# CubeSat_Backplane.net
KiCad netlist of a schematic drawn in Altium Designer
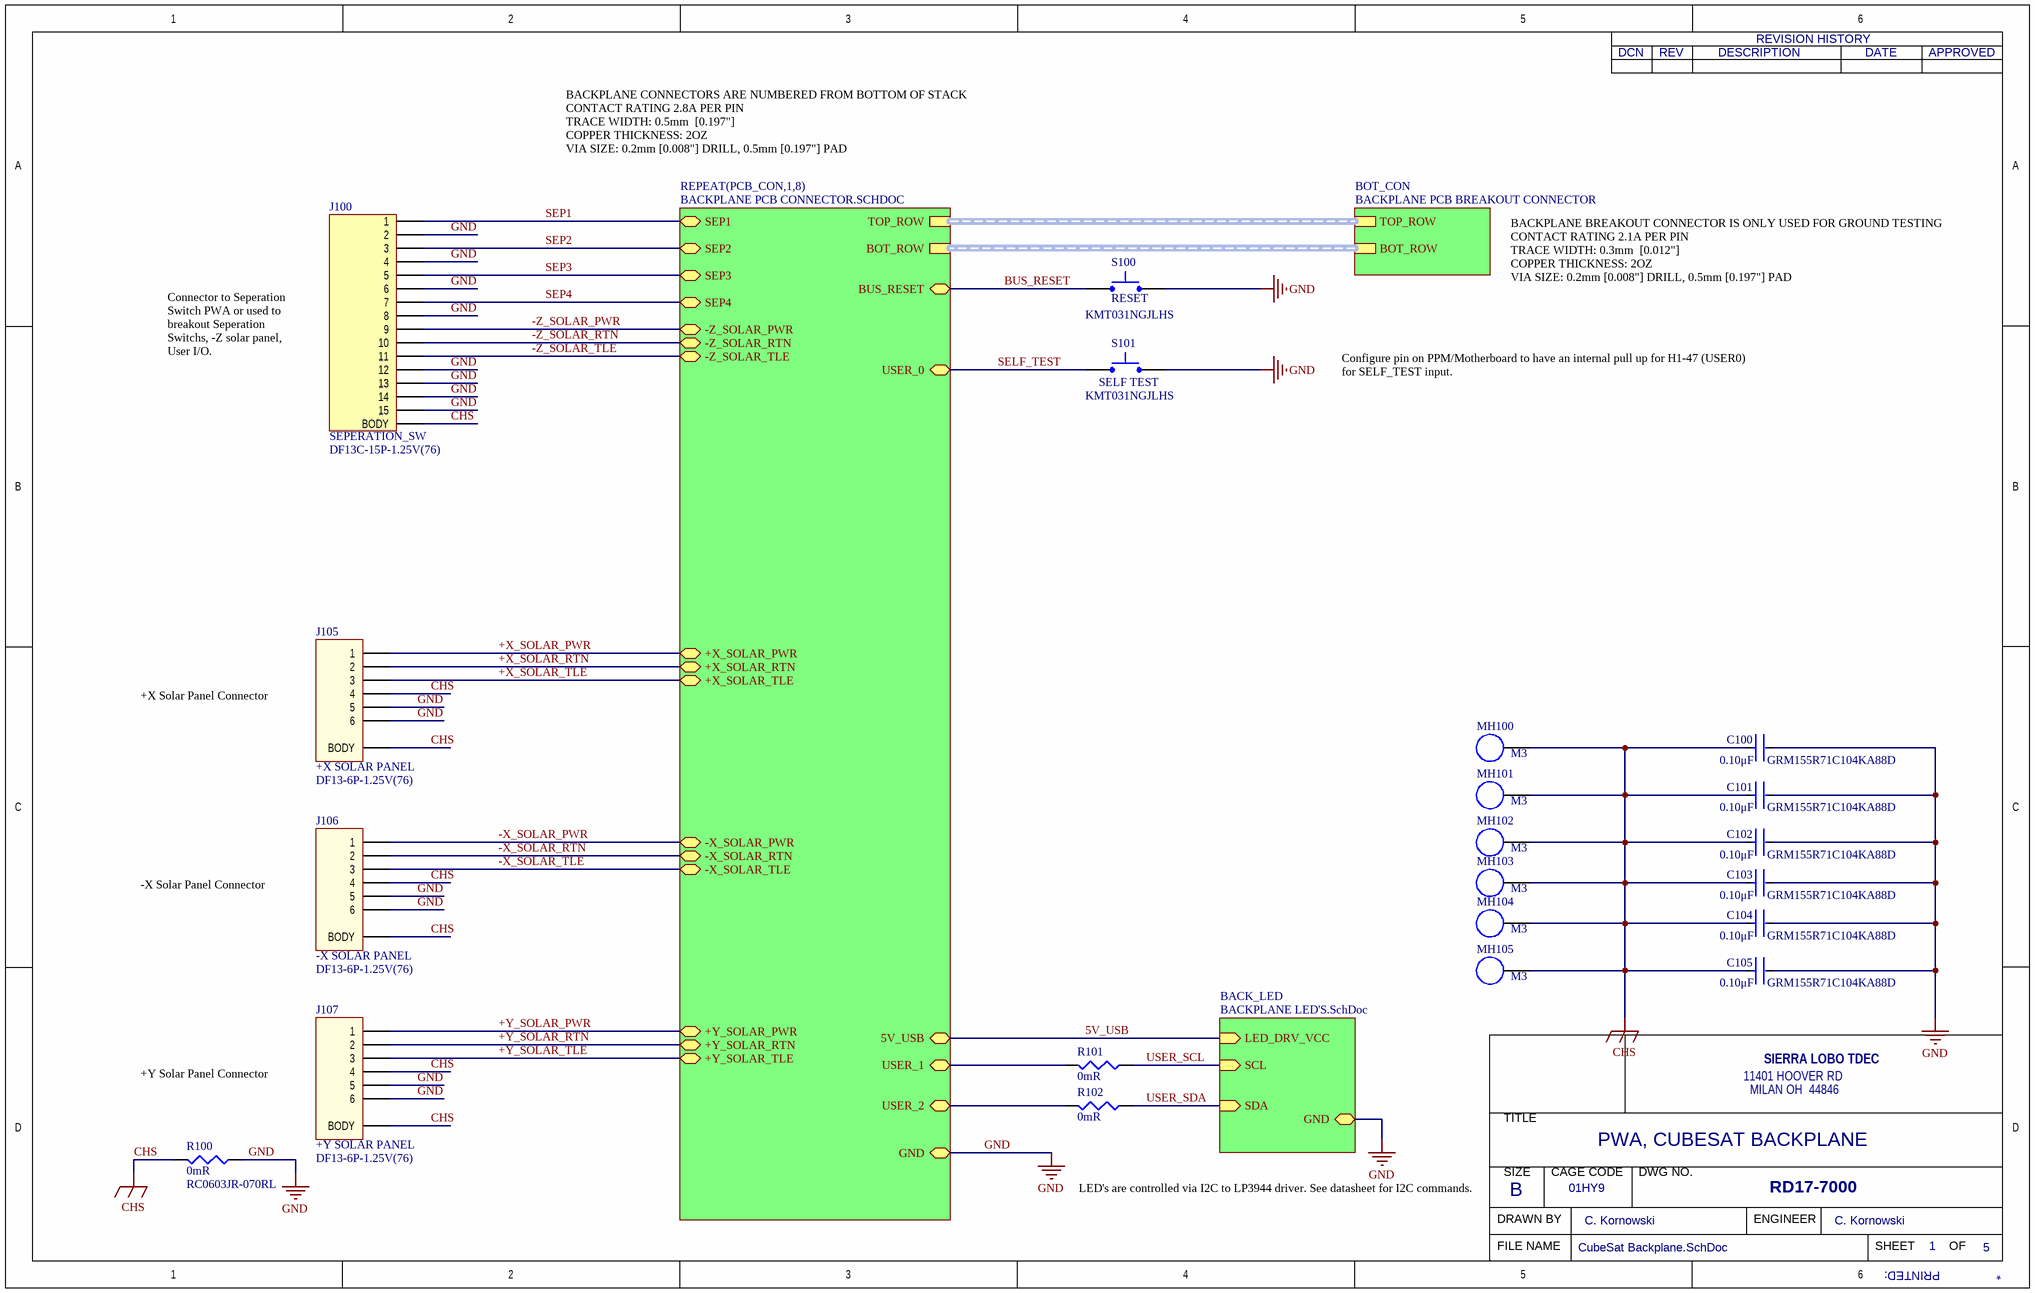
[diagram p0: CubeSat Backplane.SchDoc]

(export (version "E")
  (design (tool "Eeschema 10.0.6"))
  (components
    (comp (ref "C100")
      (value "GRM155R71C104KA88D")
      (footprint "FP-GRM15-MFG")
      (description "CAP CER 0.1UF 16V X7R 0402")
      (fields
        (field (name "TOLERANCE") "10%")
        (field (name "OCTOPART") "https://octopart.com/grm155r71c104ka88d-murata-196880")
        (field (name "CAPACITANCE") "0.10μF")
      )
      (libsource (lib "Altium Content Vault") (part "236180d848d6139a670b325ea6854c9"))
    )
    (comp (ref "C101")
      (value "GRM155R71C104KA88D")
      (footprint "FP-GRM15-MFG")
      (description "CAP CER 0.1UF 16V X7R 0402")
      (fields
        (field (name "TOLERANCE") "10%")
        (field (name "OCTOPART") "https://octopart.com/grm155r71c104ka88d-murata-196880")
        (field (name "CAPACITANCE") "0.10μF")
      )
      (libsource (lib "Altium Content Vault") (part "236180d848d6139a670b325ea6854c9"))
    )
    (comp (ref "C102")
      (value "GRM155R71C104KA88D")
      (footprint "FP-GRM15-MFG")
      (description "CAP CER 0.1UF 16V X7R 0402")
      (fields
        (field (name "TOLERANCE") "10%")
        (field (name "OCTOPART") "https://octopart.com/grm155r71c104ka88d-murata-196880")
        (field (name "CAPACITANCE") "0.10μF")
      )
      (libsource (lib "Altium Content Vault") (part "236180d848d6139a670b325ea6854c9"))
    )
    (comp (ref "C103")
      (value "GRM155R71C104KA88D")
      (footprint "FP-GRM15-MFG")
      (description "CAP CER 0.1UF 16V X7R 0402")
      (fields
        (field (name "TOLERANCE") "10%")
        (field (name "OCTOPART") "https://octopart.com/grm155r71c104ka88d-murata-196880")
        (field (name "CAPACITANCE") "0.10μF")
      )
      (libsource (lib "Altium Content Vault") (part "236180d848d6139a670b325ea6854c9"))
    )
    (comp (ref "C104")
      (value "GRM155R71C104KA88D")
      (footprint "FP-GRM15-MFG")
      (description "CAP CER 0.1UF 16V X7R 0402")
      (fields
        (field (name "TOLERANCE") "10%")
        (field (name "OCTOPART") "https://octopart.com/grm155r71c104ka88d-murata-196880")
        (field (name "CAPACITANCE") "0.10μF")
      )
      (libsource (lib "Altium Content Vault") (part "236180d848d6139a670b325ea6854c9"))
    )
    (comp (ref "C105")
      (value "GRM155R71C104KA88D")
      (footprint "FP-GRM15-MFG")
      (description "CAP CER 0.1UF 16V X7R 0402")
      (fields
        (field (name "TOLERANCE") "10%")
        (field (name "OCTOPART") "https://octopart.com/grm155r71c104ka88d-murata-196880")
        (field (name "CAPACITANCE") "0.10μF")
      )
      (libsource (lib "Altium Content Vault") (part "236180d848d6139a670b325ea6854c9"))
    )
    (comp (ref "J100")
      (value "SEPERATION_SW")
      (footprint "DF13-15P-1.25H(75)")
      (description "CONN HEADER SMD R/A 15POS 1.25MM")
      (fields
        (field (name "MANUFACTURER") "Hirose")
        (field (name "MANUFACTURER PART NUMBER") "DF13C-15P-1.25V(76)")
      )
      (libsource (lib "CubeSat-Backplane") (part "DF13C-15P-1.25x"))
    )
    (comp (ref "J105")
      (value "+X SOLAR PANEL")
      (footprint "DF13-6P-1.25V(75)")
      (description "CONN HEADER SMD 6POS 1.25MM")
      (fields (field (name "MANUFACTURER PART NUMBER 1") "DF13-6P-1.25V(76)"))
      (libsource (lib "CubeSat-Backplane") (part "DF13-6P-1.25V(76)"))
    )
    (comp (ref "J106")
      (value "-X SOLAR PANEL")
      (footprint "DF13-6P-1.25V(75)")
      (description "CONN HEADER SMD 6POS 1.25MM")
      (fields (field (name "MANUFACTURER PART NUMBER 1") "DF13-6P-1.25V(76)"))
      (libsource (lib "CubeSat-Backplane") (part "DF13-6P-1.25V(76)"))
    )
    (comp (ref "J107")
      (value "+Y SOLAR PANEL")
      (footprint "DF13-6P-1.25V(75)")
      (description "CONN HEADER SMD 6POS 1.25MM")
      (fields (field (name "MANUFACTURER PART NUMBER 1") "DF13-6P-1.25V(76)"))
      (libsource (lib "CubeSat-Backplane") (part "DF13-6P-1.25V(76)"))
    )
    (comp (ref "MH100")
      (value "M3")
      (footprint "M3_NPTH/W PAD")
      (libsource (lib "CubeSat-Backplane") (part "Mounting Hole"))
    )
    (comp (ref "MH101")
      (value "M3")
      (footprint "M3_NPTH/W PAD")
      (libsource (lib "CubeSat-Backplane") (part "Mounting Hole"))
    )
    (comp (ref "MH102")
      (value "M3")
      (footprint "M3_NPTH/W PAD")
      (libsource (lib "CubeSat-Backplane") (part "Mounting Hole"))
    )
    (comp (ref "MH103")
      (value "M3")
      (footprint "M3_NPTH/W PAD")
      (libsource (lib "CubeSat-Backplane") (part "Mounting Hole"))
    )
    (comp (ref "MH104")
      (value "M3")
      (footprint "M3_NPTH/W PAD")
      (libsource (lib "CubeSat-Backplane") (part "Mounting Hole"))
    )
    (comp (ref "MH105")
      (value "M3")
      (footprint "M3_NPTH/W PAD")
      (libsource (lib "CubeSat-Backplane") (part "Mounting Hole"))
    )
    (comp (ref "R100")
      (value "0mR")
      (footprint "0603")
      (description "RES SMD 0 OHM JUMPER 1/10W 0603")
      (fields (field (name "MANUFACTURER PART NUMBER 1") "RC0603JR-070RL") (field (name "TOLERANCE") "1%"))
      (libsource (lib "CubeSat-Backplane") (part "RES1"))
    )
    (comp (ref "R101")
      (value "0mR")
      (footprint "0603")
      (description "RES SMD 0 OHM JUMPER 1/10W 0603")
      (fields (field (name "TOLERANCE") "1%"))
      (libsource (lib "CubeSat-Backplane") (part "RES1"))
    )
    (comp (ref "R102")
      (value "0mR")
      (footprint "0603")
      (description "RES SMD 0 OHM JUMPER 1/10W 0603")
      (fields (field (name "TOLERANCE") "1%"))
      (libsource (lib "CubeSat-Backplane") (part "RES1"))
    )
    (comp (ref "S100")
      (value "RESET")
      (footprint "KMT031 NGJ LHS")
      (description "SWITCH TACTILE SPST-NO 0.05A 32V")
      (fields (field (name "MANUFACTURER PART NUMBER 1") "KMT031NGJLHS"))
      (libsource (lib "CubeSat-Backplane") (part "Tactile_Switch"))
    )
    (comp (ref "S101")
      (value "SELF TEST")
      (footprint "KMT031 NGJ LHS")
      (description "SWITCH TACTILE SPST-NO 0.05A 32V")
      (fields (field (name "MANUFACTURER PART NUMBER 1") "KMT031NGJLHS"))
      (libsource (lib "CubeSat-Backplane") (part "Tactile_Switch"))
    )
  )
  (nets
    (net (code "1") (name "/+X_SOLAR_PWR") (class "Default")
      (node (ref "J105") (pin "1") (pinfunction "1_1") (pintype "passive"))
    )
    (net (code "2") (name "/+X_SOLAR_RTN") (class "Default")
      (node (ref "J105") (pin "2") (pinfunction "2_2") (pintype "passive"))
    )
    (net (code "3") (name "/+X_SOLAR_TLE") (class "Default")
      (node (ref "J105") (pin "3") (pinfunction "3_3") (pintype "passive"))
    )
    (net (code "4") (name "/+Y_SOLAR_PWR") (class "Default")
      (node (ref "J107") (pin "1") (pinfunction "1_1") (pintype "passive"))
    )
    (net (code "5") (name "/+Y_SOLAR_RTN") (class "Default")
      (node (ref "J107") (pin "2") (pinfunction "2_2") (pintype "passive"))
    )
    (net (code "6") (name "/+Y_SOLAR_TLE") (class "Default")
      (node (ref "J107") (pin "3") (pinfunction "3_3") (pintype "passive"))
    )
    (net (code "7") (name "/-X_SOLAR_PWR") (class "Default")
      (node (ref "J106") (pin "1") (pinfunction "1_1") (pintype "passive"))
    )
    (net (code "8") (name "/-X_SOLAR_RTN") (class "Default")
      (node (ref "J106") (pin "2") (pinfunction "2_2") (pintype "passive"))
    )
    (net (code "9") (name "/-X_SOLAR_TLE") (class "Default")
      (node (ref "J106") (pin "3") (pinfunction "3_3") (pintype "passive"))
    )
    (net (code "10") (name "/-Z_SOLAR_PWR") (class "Default")
      (node (ref "J100") (pin "9") (pinfunction "9_9") (pintype "passive"))
    )
    (net (code "11") (name "/-Z_SOLAR_RTN") (class "Default")
      (node (ref "J100") (pin "10") (pinfunction "10_10") (pintype "passive"))
    )
    (net (code "12") (name "/-Z_SOLAR_TLE") (class "Default")
      (node (ref "J100") (pin "11") (pinfunction "11_11") (pintype "passive"))
    )
    (net (code "15") (name "/BUS_RESET") (class "Default")
      (node (ref "S100") (pin "1") (pinfunction "1_1") (pintype "passive"))
    )
    (net (code "16") (name "/SELF_TEST") (class "Default")
      (node (ref "S101") (pin "1") (pinfunction "1_1") (pintype "passive"))
    )
    (net (code "17") (name "/SEP1") (class "Default")
      (node (ref "J100") (pin "1") (pinfunction "1_1") (pintype "passive"))
    )
    (net (code "18") (name "/SEP2") (class "Default")
      (node (ref "J100") (pin "3") (pinfunction "3_3") (pintype "passive"))
    )
    (net (code "19") (name "/SEP3") (class "Default")
      (node (ref "J100") (pin "5") (pinfunction "5_5") (pintype "passive"))
    )
    (net (code "20") (name "/SEP4") (class "Default")
      (node (ref "J100") (pin "7") (pinfunction "7_7") (pintype "passive"))
    )
    (net (code "22") (name "/USER_1") (class "Default")
      (node (ref "R101") (pin "2") (pinfunction "2_2") (pintype "passive"))
    )
    (net (code "23") (name "/USER_2") (class "Default")
      (node (ref "R102") (pin "2") (pinfunction "2_2") (pintype "passive"))
    )
    (net (code "24") (name "/USER_SCL") (class "Default")
      (node (ref "R101") (pin "1") (pinfunction "1_1") (pintype "passive"))
    )
    (net (code "25") (name "/USER_SDA") (class "Default")
      (node (ref "R102") (pin "1") (pinfunction "1_1") (pintype "passive"))
    )
    (net (code "26") (name "CHS") (class "Default")
      (node (ref "C100") (pin "2") (pinfunction "2_2") (pintype "passive"))
      (node (ref "C101") (pin "2") (pinfunction "2_2") (pintype "passive"))
      (node (ref "C102") (pin "2") (pinfunction "2_2") (pintype "passive"))
      (node (ref "C103") (pin "2") (pinfunction "2_2") (pintype "passive"))
      (node (ref "C104") (pin "2") (pinfunction "2_2") (pintype "passive"))
      (node (ref "C105") (pin "2") (pinfunction "2_2") (pintype "passive"))
      (node (ref "J100") (pin "B") (pinfunction "BODY_B") (pintype "passive"))
      (node (ref "J105") (pin "4") (pinfunction "4_4") (pintype "passive"))
      (node (ref "J105") (pin "B") (pinfunction "BODY_B") (pintype "passive"))
      (node (ref "J106") (pin "4") (pinfunction "4_4") (pintype "passive"))
      (node (ref "J106") (pin "B") (pinfunction "BODY_B") (pintype "passive"))
      (node (ref "J107") (pin "4") (pinfunction "4_4") (pintype "passive"))
      (node (ref "J107") (pin "B") (pinfunction "BODY_B") (pintype "passive"))
      (node (ref "MH100") (pin "MH") (pinfunction "MH_MH") (pintype "passive"))
      (node (ref "MH101") (pin "MH") (pinfunction "MH_MH") (pintype "passive"))
      (node (ref "MH102") (pin "MH") (pinfunction "MH_MH") (pintype "passive"))
      (node (ref "MH103") (pin "MH") (pinfunction "MH_MH") (pintype "passive"))
      (node (ref "MH104") (pin "MH") (pinfunction "MH_MH") (pintype "passive"))
      (node (ref "MH105") (pin "MH") (pinfunction "MH_MH") (pintype "passive"))
      (node (ref "R100") (pin "2") (pinfunction "2_2") (pintype "passive"))
    )
    (net (code "27") (name "GND") (class "Default")
      (node (ref "C100") (pin "1") (pinfunction "1_1") (pintype "passive"))
      (node (ref "C101") (pin "1") (pinfunction "1_1") (pintype "passive"))
      (node (ref "C102") (pin "1") (pinfunction "1_1") (pintype "passive"))
      (node (ref "C103") (pin "1") (pinfunction "1_1") (pintype "passive"))
      (node (ref "C104") (pin "1") (pinfunction "1_1") (pintype "passive"))
      (node (ref "C105") (pin "1") (pinfunction "1_1") (pintype "passive"))
      (node (ref "J100") (pin "12") (pinfunction "12_12") (pintype "passive"))
      (node (ref "J100") (pin "13") (pinfunction "13_13") (pintype "passive"))
      (node (ref "J100") (pin "14") (pinfunction "14_14") (pintype "passive"))
      (node (ref "J100") (pin "15") (pinfunction "15_15") (pintype "passive"))
      (node (ref "J100") (pin "2") (pinfunction "2_2") (pintype "passive"))
      (node (ref "J100") (pin "4") (pinfunction "4_4") (pintype "passive"))
      (node (ref "J100") (pin "6") (pinfunction "6_6") (pintype "passive"))
      (node (ref "J100") (pin "8") (pinfunction "8_8") (pintype "passive"))
      (node (ref "J105") (pin "5") (pinfunction "5_5") (pintype "passive"))
      (node (ref "J105") (pin "6") (pinfunction "6_6") (pintype "passive"))
      (node (ref "J106") (pin "5") (pinfunction "5_5") (pintype "passive"))
      (node (ref "J106") (pin "6") (pinfunction "6_6") (pintype "passive"))
      (node (ref "J107") (pin "5") (pinfunction "5_5") (pintype "passive"))
      (node (ref "J107") (pin "6") (pinfunction "6_6") (pintype "passive"))
      (node (ref "R100") (pin "1") (pinfunction "1_1") (pintype "passive"))
      (node (ref "S100") (pin "2") (pinfunction "2_2") (pintype "passive"))
      (node (ref "S101") (pin "2") (pinfunction "2_2") (pintype "passive"))
    )
  )
)
